# Ethernet.net
KiCad netlist of a schematic drawn in Altium Designer
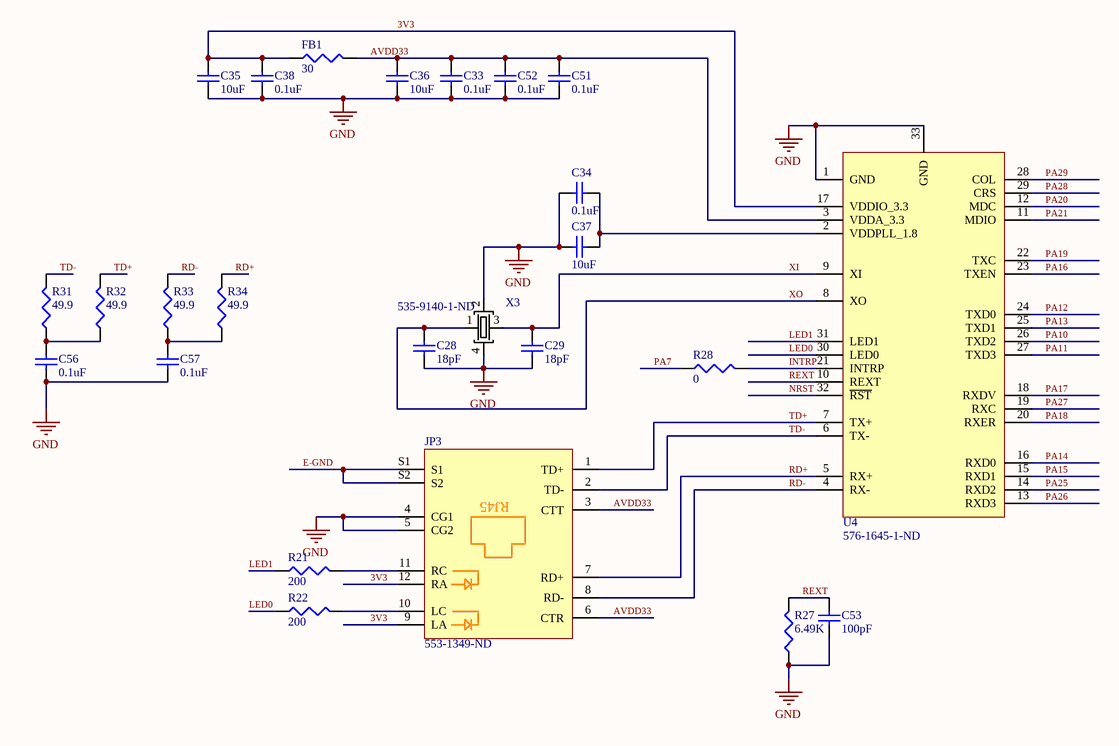
[diagram p0: Ethernet.SchDoc]

(export (version "E")
  (design (tool "Eeschema 10.0.6"))
  (components
    (comp (ref "C28")
      (value "18pF")
      (footprint "0402")
      (description "Ceramic Chip Capacitor - 18pF")
      (fields (field (name "Comment") "C0402_a_18pF") (field (name "PUBLISHER") "Altium Limited"))
      (libsource (lib "my_KEMET") (part "C0402_a_18pF"))
    )
    (comp (ref "C29")
      (value "18pF")
      (footprint "0402")
      (description "Ceramic Chip Capacitor - 18pF")
      (fields (field (name "Comment") "C0402_a_18pF") (field (name "PUBLISHER") "Altium Limited"))
      (libsource (lib "my_KEMET") (part "C0402_a_18pF"))
    )
    (comp (ref "C33")
      (value "0.1uF")
      (footprint "0402")
      (description "Ceramic Chip Capacitor - 0.1uF")
      (fields (field (name "Comment") "C0402_c_0.1uF") (field (name "PUBLISHER") "Altium Limited"))
      (libsource (lib "my_KEMET") (part "C0402_c_0.1uF"))
    )
    (comp (ref "C34")
      (value "0.1uF")
      (footprint "0402")
      (description "Ceramic Chip Capacitor - 0.1uF")
      (fields (field (name "Comment") "C0402_c_0.1uF") (field (name "PUBLISHER") "Altium Limited"))
      (libsource (lib "my_KEMET") (part "C0402_c_0.1uF"))
    )
    (comp (ref "C35")
      (value "10uF")
      (footprint "0805")
      (description "Ceramic Chip Capacitor - 10uF")
      (fields (field (name "Comment") "C0805_c_10uF") (field (name "PUBLISHER") "Altium Limited"))
      (libsource (lib "my_KEMET") (part "C0805_c_10uF"))
    )
    (comp (ref "C36")
      (value "10uF")
      (footprint "0805")
      (description "Ceramic Chip Capacitor - 10uF")
      (fields (field (name "Comment") "C0805_c_10uF") (field (name "PUBLISHER") "Altium Limited"))
      (libsource (lib "my_KEMET") (part "C0805_c_10uF"))
    )
    (comp (ref "C37")
      (value "10uF")
      (footprint "0805")
      (description "Ceramic Chip Capacitor - 10uF")
      (fields (field (name "Comment") "C0805_c_10uF") (field (name "PUBLISHER") "Altium Limited"))
      (libsource (lib "my_KEMET") (part "C0805_c_10uF"))
    )
    (comp (ref "C38")
      (value "0.1uF")
      (footprint "0402")
      (description "Ceramic Chip Capacitor - 0.1uF")
      (fields (field (name "Comment") "C0402_c_0.1uF") (field (name "PUBLISHER") "Altium Limited"))
      (libsource (lib "my_KEMET") (part "C0402_c_0.1uF"))
    )
    (comp (ref "C51")
      (value "0.1uF")
      (footprint "0402")
      (description "Ceramic Chip Capacitor - 0.1uF")
      (fields (field (name "Comment") "C0402_c_0.1uF") (field (name "PUBLISHER") "Altium Limited"))
      (libsource (lib "my_KEMET") (part "C0402_c_0.1uF"))
    )
    (comp (ref "C52")
      (value "0.1uF")
      (footprint "0402")
      (description "Ceramic Chip Capacitor - 0.1uF")
      (fields (field (name "Comment") "C0402_c_0.1uF") (field (name "PUBLISHER") "Altium Limited"))
      (libsource (lib "my_KEMET") (part "C0402_c_0.1uF"))
    )
    (comp (ref "C53")
      (value "100pF")
      (footprint "0402")
      (description "Ceramic Chip Capacitor - 100pF")
      (fields (field (name "Comment") "C0402_a_100pF") (field (name "PUBLISHER") "Altium Limited"))
      (libsource (lib "my_KEMET") (part "C0402_a_100pF"))
    )
    (comp (ref "C56")
      (value "0.1uF")
      (footprint "0402")
      (description "Ceramic Chip Capacitor - 0.1uF")
      (fields (field (name "Comment") "C0402_c_0.1uF") (field (name "PUBLISHER") "Altium Limited"))
      (libsource (lib "my_KEMET") (part "C0402_c_0.1uF"))
    )
    (comp (ref "C57")
      (value "0.1uF")
      (footprint "0402")
      (description "Ceramic Chip Capacitor - 0.1uF")
      (fields (field (name "Comment") "C0402_c_0.1uF") (field (name "PUBLISHER") "Altium Limited"))
      (libsource (lib "my_KEMET") (part "C0402_c_0.1uF"))
    )
    (comp (ref "FB1")
      (value "Murata_a_0805_30_Ohm_100Mhz")
      (footprint "0805")
      (description "FERRITE CHIP 30 OHM 3000MA 0805")
      (fields (field (name "VALUE @ 100MHZ") "30"))
      (libsource (lib "Filters") (part "Murata_a_0805_30_Ohm_100Mhz"))
    )
    (comp (ref "JP3")
      (value "Ethernet connector")
      (footprint "RJ45")
      (description "CONN PULSEJACK 1PORT 10/100B-TX")
      (fields (field (name "MANUFACTURER") "Pulse") (field (name "SUPPLIER PART NUMBER 1") "553-1349-ND"))
      (libsource (lib "Pulse") (part "Ethernet connector"))
    )
    (comp (ref "R21")
      (value "200")
      (footprint "RES0805")
      (description "RES 200 OHM 1/10W .5% 0805 SMD")
      (fields (field (name "Comment") "Susumu_0805_a3_200"))
      (libsource (lib "Resistors") (part "Susumu_0805_a3_200"))
    )
    (comp (ref "R22")
      (value "200")
      (footprint "RES0805")
      (description "RES 200 OHM 1/10W .5% 0805 SMD")
      (fields (field (name "Comment") "Susumu_0805_a3_200"))
      (libsource (lib "Resistors") (part "Susumu_0805_a3_200"))
    )
    (comp (ref "R27")
      (value "6.49K")
      (footprint "RES0805")
      (description "RES 6.49K OHM 1/4W 1% 0805 SMD")
      (fields (field (name "Comment") "Stackpole_0805_b1_6.49K"))
      (libsource (lib "Resistors") (part "Stackpole_0805_b1_6.49K"))
    )
    (comp (ref "R28")
      (value "0")
      (footprint "RES0805")
      (fields (field (name "Comment") "Vishay_0805_a1_0.0"))
      (libsource (lib "Resistors") (part "Vishay_0805_a1_0.0"))
    )
    (comp (ref "R31")
      (value "49.9")
      (footprint "RES0805")
      (description "RES 49.9 OHM 1/10W .5% 0805 SMD")
      (fields (field (name "MANUFACTURER") "Susumu") (field (name "Comment") "Susumu_0805_a1_49.9"))
      (libsource (lib "Resistors") (part "Susumu_0805_a1_49.9"))
    )
    (comp (ref "R32")
      (value "49.9")
      (footprint "RES0805")
      (description "RES 49.9 OHM 1/10W .5% 0805 SMD")
      (fields (field (name "MANUFACTURER") "Susumu") (field (name "Comment") "Susumu_0805_a1_49.9"))
      (libsource (lib "Resistors") (part "Susumu_0805_a1_49.9"))
    )
    (comp (ref "R33")
      (value "49.9")
      (footprint "RES0805")
      (description "RES 49.9 OHM 1/10W .5% 0805 SMD")
      (fields (field (name "MANUFACTURER") "Susumu") (field (name "Comment") "Susumu_0805_a1_49.9"))
      (libsource (lib "Resistors") (part "Susumu_0805_a1_49.9"))
    )
    (comp (ref "R34")
      (value "49.9")
      (footprint "RES0805")
      (description "RES 49.9 OHM 1/10W .5% 0805 SMD")
      (fields (field (name "MANUFACTURER") "Susumu") (field (name "Comment") "Susumu_0805_a1_49.9"))
      (libsource (lib "Resistors") (part "Susumu_0805_a1_49.9"))
    )
    (comp (ref "U4")
      (value "10Base-T/100Base-TX Physical Layer Transceiver")
      (footprint "QFN50P500X500X85-32N")
      (fields
        (field (name "MANUFACTURER") "Micrel INC.")
        (field (name "SUPPLIER PART NUMBER 1") "576-1645-1-ND")
      )
      (libsource (lib "Micrel INC") (part "10Base-T/100Base-TX Physical Layer Transceiver"))
    )
    (comp (ref "X3")
      (value "Crystal_25.000MHz")
      (footprint "Crystal Footprint")
      (description "Crystal 25.000MHz 18PF SMD")
      (fields
        (field (name "MANUFACTURER") "Abracon Corporation")
        (field (name "SUPPLIER PART NUMBER 1") "535-9140-1-ND")
      )
      (libsource (lib "Abracon Corporation") (part "Crystal_25.000MHz"))
    )
  )
  (nets
    (net (code "1") (name "/3V3") (class "Default")
      (node (ref "C35") (pin "2") (pinfunction "2_2") (pintype "passive"))
      (node (ref "C38") (pin "2") (pinfunction "2_2") (pintype "passive"))
      (node (ref "FB1") (pin "1") (pinfunction "1_1") (pintype "passive"))
      (node (ref "JP3") (pin "12") (pinfunction "RA_12") (pintype "passive"))
      (node (ref "JP3") (pin "9") (pinfunction "LA_9") (pintype "passive"))
      (node (ref "U4") (pin "17") (pinfunction "VDDIO_3.3_17") (pintype "passive"))
    )
    (net (code "2") (name "/AVDD33") (class "Default")
      (node (ref "C33") (pin "2") (pinfunction "2_2") (pintype "passive"))
      (node (ref "C36") (pin "2") (pinfunction "2_2") (pintype "passive"))
      (node (ref "C51") (pin "2") (pinfunction "2_2") (pintype "passive"))
      (node (ref "C52") (pin "2") (pinfunction "2_2") (pintype "passive"))
      (node (ref "FB1") (pin "2") (pinfunction "2_2") (pintype "passive"))
      (node (ref "JP3") (pin "3") (pinfunction "CTT_3") (pintype "power_in"))
      (node (ref "JP3") (pin "6") (pinfunction "CTR_6") (pintype "power_in"))
      (node (ref "U4") (pin "3") (pinfunction "VDDA_3.3_3") (pintype "passive"))
    )
    (net (code "3") (name "/E-GND") (class "Default")
      (node (ref "JP3") (pin "S1") (pinfunction "S1_S1") (pintype "passive"))
      (node (ref "JP3") (pin "S2") (pinfunction "S2_S2") (pintype "passive"))
    )
    (net (code "4") (name "/INTRP") (class "Default")
      (node (ref "R28") (pin "2") (pinfunction "2_2") (pintype "passive"))
      (node (ref "U4") (pin "21") (pinfunction "INTRP_21") (pintype "passive"))
    )
    (net (code "5") (name "/LED0") (class "Default")
      (node (ref "R22") (pin "1") (pinfunction "1_1") (pintype "passive"))
      (node (ref "U4") (pin "30") (pinfunction "LED0_30") (pintype "passive"))
    )
    (net (code "6") (name "/LED1") (class "Default")
      (node (ref "R21") (pin "1") (pinfunction "1_1") (pintype "passive"))
      (node (ref "U4") (pin "31") (pinfunction "LED1_31") (pintype "passive"))
    )
    (net (code "7") (name "/NRST") (class "Default")
      (node (ref "U4") (pin "32") (pinfunction "~{RST}_32") (pintype "passive"))
    )
    (net (code "8") (name "/PA7") (class "Default")
      (node (ref "R28") (pin "1") (pinfunction "1_1") (pintype "passive"))
    )
    (net (code "9") (name "/PA10") (class "Default")
      (node (ref "U4") (pin "26") (pinfunction "TXD2_26") (pintype "passive"))
    )
    (net (code "10") (name "/PA11") (class "Default")
      (node (ref "U4") (pin "27") (pinfunction "TXD3_27") (pintype "passive"))
    )
    (net (code "11") (name "/PA12") (class "Default")
      (node (ref "U4") (pin "24") (pinfunction "TXD0_24") (pintype "passive"))
    )
    (net (code "12") (name "/PA13") (class "Default")
      (node (ref "U4") (pin "25") (pinfunction "TXD1_25") (pintype "passive"))
    )
    (net (code "13") (name "/PA14") (class "Default")
      (node (ref "U4") (pin "16") (pinfunction "RXD0_16") (pintype "passive"))
    )
    (net (code "14") (name "/PA15") (class "Default")
      (node (ref "U4") (pin "15") (pinfunction "RXD1_15") (pintype "passive"))
    )
    (net (code "15") (name "/PA16") (class "Default")
      (node (ref "U4") (pin "23") (pinfunction "TXEN_23") (pintype "passive"))
    )
    (net (code "16") (name "/PA17") (class "Default")
      (node (ref "U4") (pin "18") (pinfunction "RXDV_18") (pintype "passive"))
    )
    (net (code "17") (name "/PA18") (class "Default")
      (node (ref "U4") (pin "20") (pinfunction "RXER_20") (pintype "passive"))
    )
    (net (code "18") (name "/PA19") (class "Default")
      (node (ref "U4") (pin "22") (pinfunction "TXC_22") (pintype "passive"))
    )
    (net (code "19") (name "/PA20") (class "Default")
      (node (ref "U4") (pin "12") (pinfunction "MDC_12") (pintype "passive"))
    )
    (net (code "20") (name "/PA21") (class "Default")
      (node (ref "U4") (pin "11") (pinfunction "MDIO_11") (pintype "passive"))
    )
    (net (code "21") (name "/PA25") (class "Default")
      (node (ref "U4") (pin "14") (pinfunction "RXD2_14") (pintype "passive"))
    )
    (net (code "22") (name "/PA26") (class "Default")
      (node (ref "U4") (pin "13") (pinfunction "RXD3_13") (pintype "passive"))
    )
    (net (code "23") (name "/PA27") (class "Default")
      (node (ref "U4") (pin "19") (pinfunction "RXC_19") (pintype "passive"))
    )
    (net (code "24") (name "/PA28") (class "Default")
      (node (ref "U4") (pin "29") (pinfunction "CRS_29") (pintype "passive"))
    )
    (net (code "25") (name "/PA29") (class "Default")
      (node (ref "U4") (pin "28") (pinfunction "COL_28") (pintype "passive"))
    )
    (net (code "26") (name "/RD+") (class "Default")
      (node (ref "JP3") (pin "7") (pinfunction "RD+_7") (pintype "passive"))
      (node (ref "R34") (pin "2") (pinfunction "2_2") (pintype "passive"))
      (node (ref "U4") (pin "5") (pinfunction "RX+_5") (pintype "passive"))
    )
    (net (code "27") (name "/RD-") (class "Default")
      (node (ref "JP3") (pin "8") (pinfunction "RD-_8") (pintype "passive"))
      (node (ref "R33") (pin "2") (pinfunction "2_2") (pintype "passive"))
      (node (ref "U4") (pin "4") (pinfunction "RX-_4") (pintype "passive"))
    )
    (net (code "28") (name "/REXT") (class "Default")
      (node (ref "C53") (pin "2") (pinfunction "2_2") (pintype "passive"))
      (node (ref "R27") (pin "2") (pinfunction "2_2") (pintype "passive"))
      (node (ref "U4") (pin "10") (pinfunction "REXT_10") (pintype "passive"))
    )
    (net (code "29") (name "/TD+") (class "Default")
      (node (ref "JP3") (pin "1") (pinfunction "TD+_1") (pintype "passive"))
      (node (ref "R32") (pin "2") (pinfunction "2_2") (pintype "passive"))
      (node (ref "U4") (pin "7") (pinfunction "TX+_7") (pintype "passive"))
    )
    (net (code "30") (name "/TD-") (class "Default")
      (node (ref "JP3") (pin "2") (pinfunction "TD-_2") (pintype "passive"))
      (node (ref "R31") (pin "2") (pinfunction "2_2") (pintype "passive"))
      (node (ref "U4") (pin "6") (pinfunction "TX-_6") (pintype "passive"))
    )
    (net (code "31") (name "/XI") (class "Default")
      (node (ref "C29") (pin "2") (pinfunction "2_2") (pintype "passive"))
      (node (ref "U4") (pin "9") (pinfunction "XI_9") (pintype "passive"))
      (node (ref "X3") (pin "3") (pintype "passive"))
    )
    (net (code "32") (name "/XO") (class "Default")
      (node (ref "C28") (pin "2") (pinfunction "2_2") (pintype "passive"))
      (node (ref "U4") (pin "8") (pinfunction "XO_8") (pintype "passive"))
      (node (ref "X3") (pin "1") (pintype "passive"))
    )
    (net (code "33") (name "GND") (class "Default")
      (node (ref "C28") (pin "1") (pinfunction "1_1") (pintype "passive"))
      (node (ref "C29") (pin "1") (pinfunction "1_1") (pintype "passive"))
      (node (ref "C33") (pin "1") (pinfunction "1_1") (pintype "passive"))
      (node (ref "C34") (pin "1") (pinfunction "1_1") (pintype "passive"))
      (node (ref "C35") (pin "1") (pinfunction "1_1") (pintype "passive"))
      (node (ref "C36") (pin "1") (pinfunction "1_1") (pintype "passive"))
      (node (ref "C37") (pin "1") (pinfunction "1_1") (pintype "passive"))
      (node (ref "C38") (pin "1") (pinfunction "1_1") (pintype "passive"))
      (node (ref "C51") (pin "1") (pinfunction "1_1") (pintype "passive"))
      (node (ref "C52") (pin "1") (pinfunction "1_1") (pintype "passive"))
      (node (ref "C53") (pin "1") (pinfunction "1_1") (pintype "passive"))
      (node (ref "C56") (pin "1") (pinfunction "1_1") (pintype "passive"))
      (node (ref "C57") (pin "1") (pinfunction "1_1") (pintype "passive"))
      (node (ref "JP3") (pin "4") (pinfunction "CG1_4") (pintype "power_in"))
      (node (ref "JP3") (pin "5") (pinfunction "CG2_5") (pintype "power_in"))
      (node (ref "R27") (pin "1") (pinfunction "1_1") (pintype "passive"))
      (node (ref "U4") (pin "1") (pinfunction "GND_1") (pintype "passive"))
      (node (ref "U4") (pin "33") (pinfunction "GND_33") (pintype "passive"))
      (node (ref "X3") (pin "2") (pinfunction "GND_2") (pintype "passive"))
      (node (ref "X3") (pin "4") (pinfunction "GND_4") (pintype "passive"))
    )
    (net (code "34") (name "Net-(C56-Pad2)") (class "Default")
      (node (ref "C56") (pin "2") (pinfunction "2_2") (pintype "passive"))
      (node (ref "R31") (pin "1") (pinfunction "1_1") (pintype "passive"))
      (node (ref "R32") (pin "1") (pinfunction "1_1") (pintype "passive"))
    )
    (net (code "35") (name "Net-(C57-Pad2)") (class "Default")
      (node (ref "C57") (pin "2") (pinfunction "2_2") (pintype "passive"))
      (node (ref "R33") (pin "1") (pinfunction "1_1") (pintype "passive"))
      (node (ref "R34") (pin "1") (pinfunction "1_1") (pintype "passive"))
    )
    (net (code "36") (name "Net-(JP3-LC)") (class "Default")
      (node (ref "JP3") (pin "10") (pinfunction "LC_10") (pintype "passive"))
      (node (ref "R22") (pin "2") (pinfunction "2_2") (pintype "passive"))
    )
    (net (code "37") (name "Net-(JP3-RC)") (class "Default")
      (node (ref "JP3") (pin "11") (pinfunction "RC_11") (pintype "passive"))
      (node (ref "R21") (pin "2") (pinfunction "2_2") (pintype "passive"))
    )
    (net (code "38") (name "Net-(U4-VDDPLL_1.8)") (class "Default")
      (node (ref "C34") (pin "2") (pinfunction "2_2") (pintype "passive"))
      (node (ref "C37") (pin "2") (pinfunction "2_2") (pintype "passive"))
      (node (ref "U4") (pin "2") (pinfunction "VDDPLL_1.8_2") (pintype "passive"))
    )
  )
)
